# XJK1310-BT.net
KiCad netlist of a schematic drawn in EAGLE
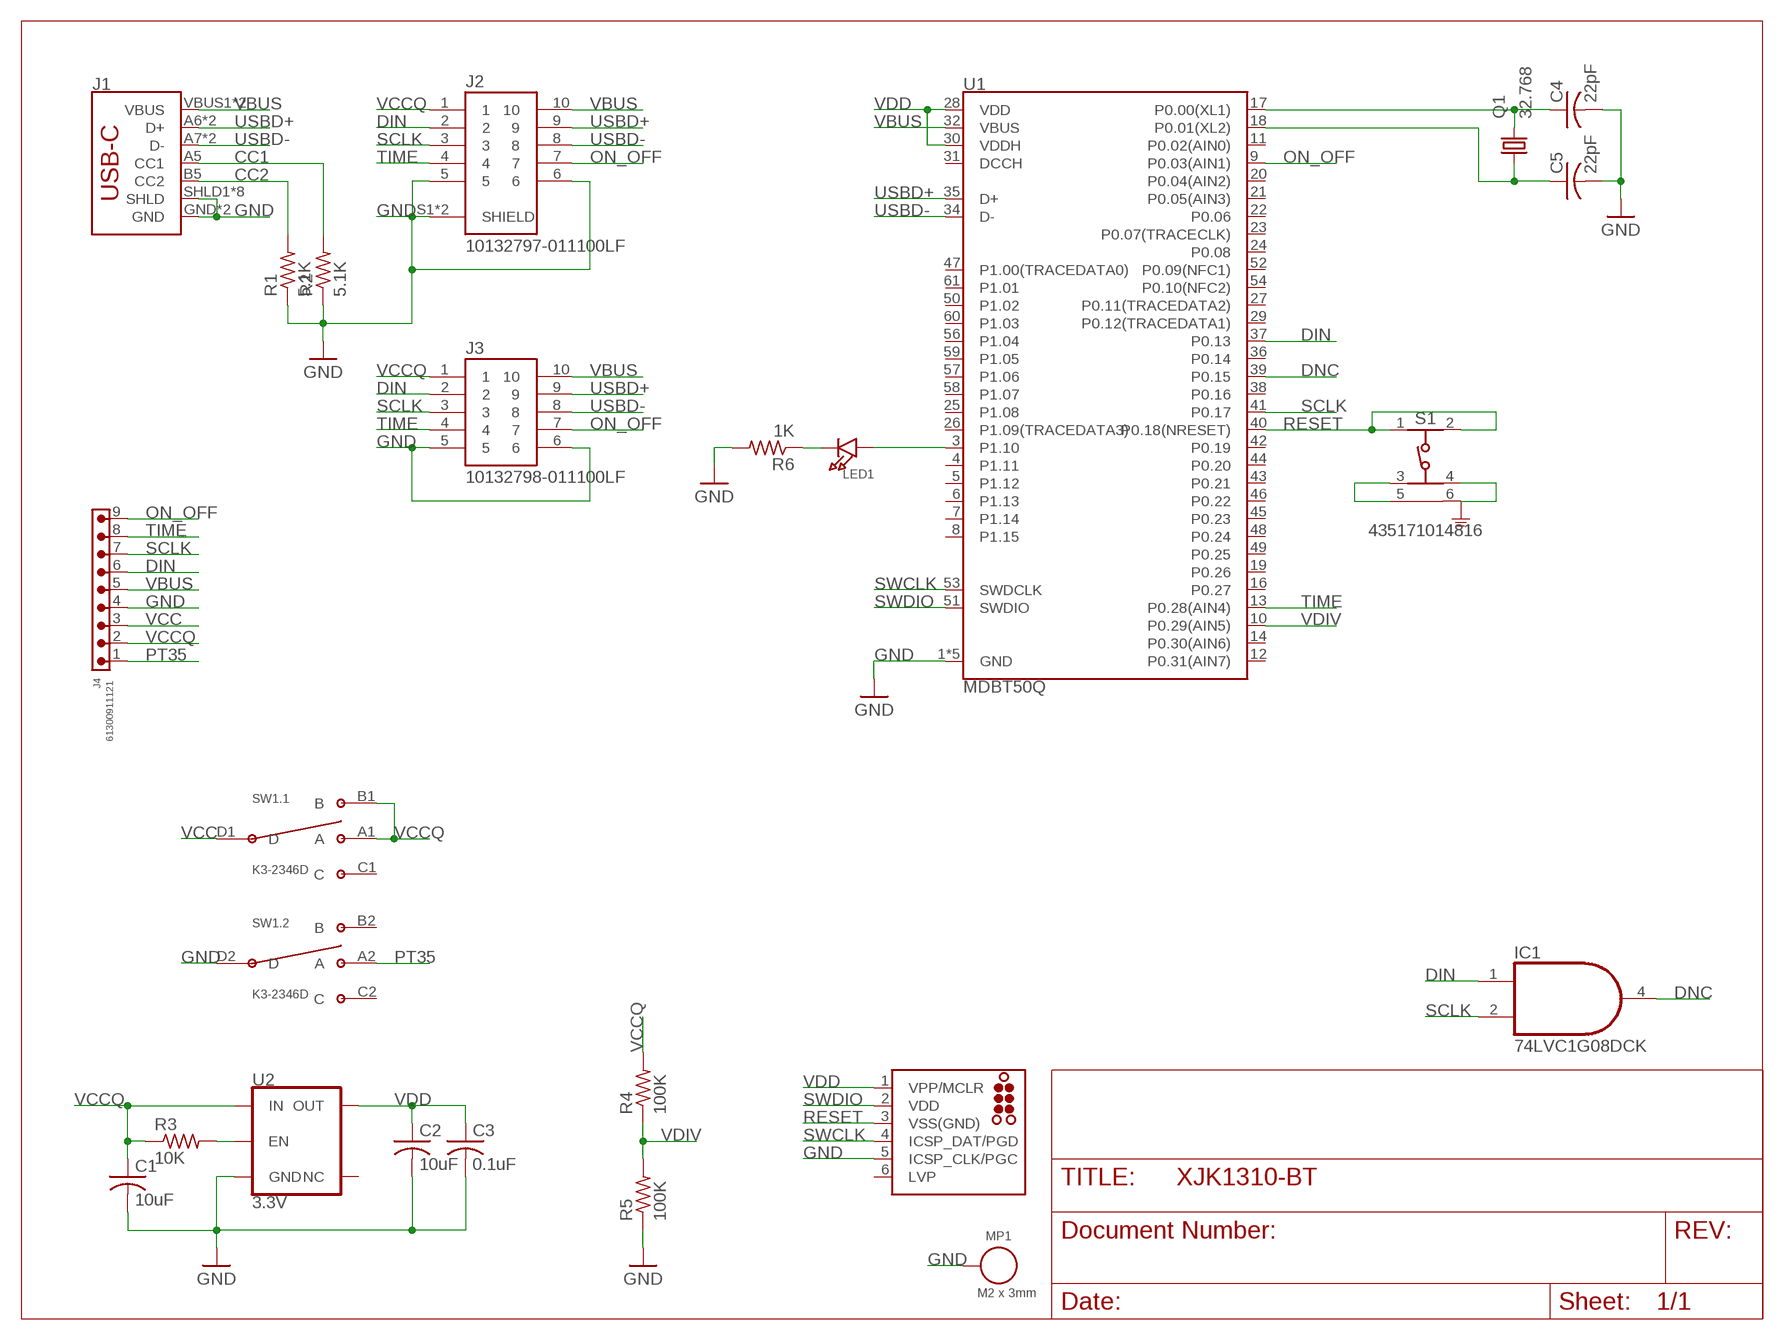
[diagram p0: schematic, sheet 1]

(export (version "E")
  (design (tool "Eeschema 10.0.6"))
  (components
    (comp (ref "C1")
      (value "10uF")
      (footprint "eagle-import:C0603")
      (libsource (lib "eagle-import") (part "C-USC0603"))
    )
    (comp (ref "C2")
      (value "10uF")
      (footprint "eagle-import:C0603")
      (libsource (lib "eagle-import") (part "C-USC0603"))
    )
    (comp (ref "C3")
      (value "0.1uF")
      (footprint "eagle-import:C0603")
      (libsource (lib "eagle-import") (part "C-USC0603"))
    )
    (comp (ref "C4")
      (value "22pF")
      (footprint "eagle-import:C0402")
      (libsource (lib "eagle-import") (part "C-USC0402"))
    )
    (comp (ref "C5")
      (value "22pF")
      (footprint "eagle-import:C0402")
      (libsource (lib "eagle-import") (part "C-USC0402"))
    )
    (comp (ref "IC1")
      (value "74LVC1G08DCK")
      (footprint "eagle-import:SC70-5")
      (libsource (lib "eagle-import") (part "741G08DCKLVC"))
    )
    (comp (ref "J1")
      (value "USB_C5")
      (footprint "eagle-import:USB-C-16P-5")
      (libsource (lib "eagle-import") (part "USB_C5"))
    )
    (comp (ref "J2")
      (value "10132797-011100LF")
      (footprint "eagle-import:AMPHENOL_10132797-011100LF")
      (fields (field (name "MANUFACTURER") "Amphenol"))
      (libsource (lib "eagle-import") (part "10132797-011100LF"))
    )
    (comp (ref "J3")
      (value "10132798-011100LF")
      (footprint "eagle-import:AMPHENOL_10132798-011100LF")
      (fields (field (name "MANUFACTURER") "Amphenol"))
      (libsource (lib "eagle-import") (part "10132798-011100LF"))
    )
    (comp (ref "J4")
      (value "61300911121")
      (footprint "eagle-import:61300911121")
      (libsource (lib "eagle-import") (part "6130XX11121_61300911121"))
    )
    (comp (ref "J5")
      (value "TC2030-MCP-NL")
      (footprint "eagle-import:TC2030-MCP-NL")
      (libsource (lib "eagle-import") (part "TC2030-MCP-NL"))
    )
    (comp (ref "LED1")
      (value "LED0805_NOOUTLINE")
      (footprint "eagle-import:CHIPLED_0805_NOOUTLINE")
      (libsource (lib "eagle-import") (part "LED0805_NOOUTLINE"))
    )
    (comp (ref "MP1")
      (value "M2 x 3mm")
      (footprint "eagle-import:WA-SMSI_9774030243")
      (libsource (lib "eagle-import") (part "WA-SMSI_9774XXX243_9774030243R"))
    )
    (comp (ref "Q1")
      (value "32.768")
      (footprint "eagle-import:3.2X1.5")
      (libsource (lib "eagle-import") (part "KX-327-NHF"))
    )
    (comp (ref "R1")
      (value "5.1K")
      (footprint "eagle-import:R0402")
      (libsource (lib "eagle-import") (part "R-US_R0402"))
    )
    (comp (ref "R2")
      (value "5.1K")
      (footprint "eagle-import:R0402")
      (libsource (lib "eagle-import") (part "R-US_R0402"))
    )
    (comp (ref "R3")
      (value "10K")
      (footprint "eagle-import:R0402")
      (libsource (lib "eagle-import") (part "R-US_R0402"))
    )
    (comp (ref "R4")
      (value "100K")
      (footprint "eagle-import:R0402")
      (libsource (lib "eagle-import") (part "R-US_R0402"))
    )
    (comp (ref "R5")
      (value "100K")
      (footprint "eagle-import:R0402")
      (libsource (lib "eagle-import") (part "R-US_R0402"))
    )
    (comp (ref "R6")
      (value "1K")
      (footprint "eagle-import:R0402")
      (libsource (lib "eagle-import") (part "R-US_R0402"))
    )
    (comp (ref "S1")
      (value "435171014816")
      (footprint "eagle-import:435171014816")
      (libsource (lib "eagle-import") (part "435171014816"))
    )
    (comp (ref "SW1")
      (value "K3-2346D")
      (footprint "eagle-import:K3-2346D")
      (fields (field (name "LCSC") "C145839"))
      (libsource (lib "eagle-import") (part "K3-2346D"))
    )
    (comp (ref "U1")
      (value "MDBT50Q")
      (footprint "eagle-import:MDBT50Q")
      (libsource (lib "eagle-import") (part "MDBT50Q"))
    )
    (comp (ref "U2")
      (value "3.3V")
      (footprint "eagle-import:SOT23-5")
      (libsource (lib "eagle-import") (part "V_REG_AP2112K-3.3V"))
    )
  )
  (nets
    (net (code "1") (name "/CC1") (class "Default")
      (node (ref "J1") (pin "A5") (pinfunction "CC1_A5") (pintype "bidirectional"))
      (node (ref "R2") (pin "2") (pinfunction "2_2") (pintype "passive"))
    )
    (net (code "2") (name "/CC2") (class "Default")
      (node (ref "J1") (pin "B5") (pinfunction "CC2_B5") (pintype "bidirectional"))
      (node (ref "R1") (pin "2") (pinfunction "2_2") (pintype "passive"))
    )
    (net (code "3") (name "/DIN") (class "Default")
      (node (ref "IC1") (pin "1") (pinfunction "I0_1") (pintype "input"))
      (node (ref "J2") (pin "2") (pinfunction "2_2") (pintype "passive"))
      (node (ref "J3") (pin "2") (pinfunction "2_2") (pintype "passive"))
      (node (ref "J4") (pin "6") (pinfunction "6_6") (pintype "passive"))
      (node (ref "U1") (pin "37") (pinfunction "P0.13_37") (pintype "bidirectional"))
    )
    (net (code "4") (name "/DNC") (class "Default")
      (node (ref "IC1") (pin "4") (pinfunction "O_4") (pintype "output"))
      (node (ref "U1") (pin "39") (pinfunction "P0.15_39") (pintype "bidirectional"))
    )
    (net (code "5") (name "/ON_OFF") (class "Default")
      (node (ref "J2") (pin "7") (pinfunction "7_7") (pintype "passive"))
      (node (ref "J3") (pin "7") (pinfunction "7_7") (pintype "passive"))
      (node (ref "J4") (pin "9") (pinfunction "9_9") (pintype "passive"))
      (node (ref "U1") (pin "9") (pinfunction "P0.03(AIN1)_9") (pintype "bidirectional"))
    )
    (net (code "6") (name "/PT35") (class "Default")
      (node (ref "J4") (pin "1") (pinfunction "1_1") (pintype "passive"))
      (node (ref "SW1") (pin "A2") (pinfunction "A_A2") (pintype "bidirectional"))
    )
    (net (code "7") (name "/RESET") (class "Default")
      (node (ref "J5") (pin "3") (pinfunction "VSS(GND)_3") (pintype "power_in"))
      (node (ref "S1") (pin "1") (pinfunction "1_1") (pintype "passive"))
      (node (ref "S1") (pin "2") (pinfunction "2_2") (pintype "passive"))
      (node (ref "U1") (pin "40") (pinfunction "P0.18(NRESET)_40") (pintype "bidirectional"))
    )
    (net (code "8") (name "/SCLK") (class "Default")
      (node (ref "IC1") (pin "2") (pinfunction "I1_2") (pintype "input"))
      (node (ref "J2") (pin "3") (pinfunction "3_3") (pintype "passive"))
      (node (ref "J3") (pin "3") (pinfunction "3_3") (pintype "passive"))
      (node (ref "J4") (pin "7") (pinfunction "7_7") (pintype "passive"))
      (node (ref "U1") (pin "41") (pinfunction "P0.17_41") (pintype "bidirectional"))
    )
    (net (code "9") (name "/SWCLK") (class "Default")
      (node (ref "J5") (pin "4") (pinfunction "ICSP_DAT/PGD_4") (pintype "bidirectional"))
      (node (ref "U1") (pin "53") (pinfunction "SWDCLK_53") (pintype "bidirectional"))
    )
    (net (code "10") (name "/SWDIO") (class "Default")
      (node (ref "J5") (pin "2") (pinfunction "VDD_2") (pintype "power_in"))
      (node (ref "U1") (pin "51") (pinfunction "SWDIO_51") (pintype "bidirectional"))
    )
    (net (code "11") (name "/TIME") (class "Default")
      (node (ref "J2") (pin "4") (pinfunction "4_4") (pintype "passive"))
      (node (ref "J3") (pin "4") (pinfunction "4_4") (pintype "passive"))
      (node (ref "J4") (pin "8") (pinfunction "8_8") (pintype "passive"))
      (node (ref "U1") (pin "13") (pinfunction "P0.28(AIN4)_13") (pintype "bidirectional"))
    )
    (net (code "12") (name "/USBD+") (class "Default")
      (node (ref "J1") (pin "A6") (pinfunction "D+_A6") (pintype "bidirectional"))
      (node (ref "J1") (pin "B6") (pinfunction "D+_B6") (pintype "bidirectional"))
      (node (ref "J2") (pin "9") (pinfunction "9_9") (pintype "passive"))
      (node (ref "J3") (pin "9") (pinfunction "9_9") (pintype "passive"))
      (node (ref "U1") (pin "35") (pinfunction "D+_35") (pintype "bidirectional"))
    )
    (net (code "13") (name "/USBD-") (class "Default")
      (node (ref "J1") (pin "A7") (pinfunction "D-_A7") (pintype "bidirectional"))
      (node (ref "J1") (pin "B7") (pinfunction "D-_B7") (pintype "bidirectional"))
      (node (ref "J2") (pin "8") (pinfunction "8_8") (pintype "passive"))
      (node (ref "J3") (pin "8") (pinfunction "8_8") (pintype "passive"))
      (node (ref "U1") (pin "34") (pinfunction "D-_34") (pintype "bidirectional"))
    )
    (net (code "14") (name "/VBUS") (class "Default")
      (node (ref "J1") (pin "VBUS1") (pinfunction "VBUS_VBUS1") (pintype "bidirectional"))
      (node (ref "J1") (pin "VBUS2") (pinfunction "VBUS_VBUS2") (pintype "bidirectional"))
      (node (ref "J2") (pin "10") (pinfunction "10_10") (pintype "passive"))
      (node (ref "J3") (pin "10") (pinfunction "10_10") (pintype "passive"))
      (node (ref "J4") (pin "5") (pinfunction "5_5") (pintype "passive"))
      (node (ref "U1") (pin "32") (pinfunction "VBUS_32") (pintype "bidirectional"))
    )
    (net (code "15") (name "/VCC") (class "Default")
      (node (ref "J4") (pin "3") (pinfunction "3_3") (pintype "passive"))
      (node (ref "SW1") (pin "D1") (pinfunction "D_D1") (pintype "bidirectional"))
    )
    (net (code "16") (name "/VCCQ") (class "Default")
      (node (ref "C1") (pin "1") (pinfunction "1_1") (pintype "passive"))
      (node (ref "J2") (pin "1") (pinfunction "1_1") (pintype "passive"))
      (node (ref "J3") (pin "1") (pinfunction "1_1") (pintype "passive"))
      (node (ref "J4") (pin "2") (pinfunction "2_2") (pintype "passive"))
      (node (ref "R3") (pin "1") (pinfunction "1_1") (pintype "passive"))
      (node (ref "R4") (pin "2") (pinfunction "2_2") (pintype "passive"))
      (node (ref "SW1") (pin "A1") (pinfunction "A_A1") (pintype "bidirectional"))
      (node (ref "SW1") (pin "B1") (pinfunction "B_B1") (pintype "bidirectional"))
      (node (ref "U2") (pin "1") (pinfunction "IN_1") (pintype "input"))
    )
    (net (code "17") (name "/VDD") (class "Default")
      (node (ref "C2") (pin "1") (pinfunction "1_1") (pintype "passive"))
      (node (ref "C3") (pin "1") (pinfunction "1_1") (pintype "passive"))
      (node (ref "J5") (pin "1") (pinfunction "VPP/MCLR_1") (pintype "passive"))
      (node (ref "U1") (pin "28") (pinfunction "VDD_28") (pintype "bidirectional"))
      (node (ref "U1") (pin "30") (pinfunction "VDDH_30") (pintype "bidirectional"))
      (node (ref "U2") (pin "5") (pinfunction "OUT_5") (pintype "passive"))
    )
    (net (code "18") (name "/VDIV") (class "Default")
      (node (ref "R4") (pin "1") (pinfunction "1_1") (pintype "passive"))
      (node (ref "R5") (pin "2") (pinfunction "2_2") (pintype "passive"))
      (node (ref "U1") (pin "10") (pinfunction "P0.29(AIN5)_10") (pintype "bidirectional"))
    )
    (net (code "19") (name "GND") (class "Default")
      (node (ref "C1") (pin "2") (pinfunction "2_2") (pintype "passive"))
      (node (ref "C2") (pin "2") (pinfunction "2_2") (pintype "passive"))
      (node (ref "C3") (pin "2") (pinfunction "2_2") (pintype "passive"))
      (node (ref "C4") (pin "2") (pinfunction "2_2") (pintype "passive"))
      (node (ref "C5") (pin "2") (pinfunction "2_2") (pintype "passive"))
      (node (ref "J1") (pin "GND") (pinfunction "GND_GND") (pintype "bidirectional"))
      (node (ref "J1") (pin "GND2") (pinfunction "GND_GND2") (pintype "bidirectional"))
      (node (ref "J1") (pin "SHLD1") (pinfunction "SHLD_SHLD1") (pintype "bidirectional"))
      (node (ref "J1") (pin "SHLD2") (pinfunction "SHLD_SHLD2") (pintype "bidirectional"))
      (node (ref "J1") (pin "SHLD3") (pinfunction "SHLD_SHLD3") (pintype "bidirectional"))
      (node (ref "J1") (pin "SHLD4") (pinfunction "SHLD_SHLD4") (pintype "bidirectional"))
      (node (ref "J1") (pin "SHLD5") (pinfunction "SHLD_SHLD5") (pintype "bidirectional"))
      (node (ref "J1") (pin "SHLD6") (pinfunction "SHLD_SHLD6") (pintype "bidirectional"))
      (node (ref "J1") (pin "SHLD7") (pinfunction "SHLD_SHLD7") (pintype "bidirectional"))
      (node (ref "J1") (pin "SHLD8") (pinfunction "SHLD_SHLD8") (pintype "bidirectional"))
      (node (ref "J2") (pin "5") (pinfunction "5_5") (pintype "passive"))
      (node (ref "J2") (pin "6") (pinfunction "6_6") (pintype "passive"))
      (node (ref "J2") (pin "S1") (pinfunction "SHIELD_S1") (pintype "passive"))
      (node (ref "J2") (pin "S2") (pinfunction "SHIELD_S2") (pintype "passive"))
      (node (ref "J3") (pin "5") (pinfunction "5_5") (pintype "passive"))
      (node (ref "J3") (pin "6") (pinfunction "6_6") (pintype "passive"))
      (node (ref "J4") (pin "4") (pinfunction "4_4") (pintype "passive"))
      (node (ref "J5") (pin "5") (pinfunction "ICSP_CLK/PGC_5") (pintype "output"))
      (node (ref "MP1") (pin "1") (pinfunction "1_1") (pintype "passive"))
      (node (ref "R1") (pin "1") (pinfunction "1_1") (pintype "passive"))
      (node (ref "R2") (pin "1") (pinfunction "1_1") (pintype "passive"))
      (node (ref "R5") (pin "1") (pinfunction "1_1") (pintype "passive"))
      (node (ref "R6") (pin "2") (pinfunction "2_2") (pintype "passive"))
      (node (ref "S1") (pin "3") (pinfunction "3_3") (pintype "passive"))
      (node (ref "S1") (pin "4") (pinfunction "4_4") (pintype "passive"))
      (node (ref "S1") (pin "5") (pinfunction "5_5") (pintype "passive"))
      (node (ref "S1") (pin "6") (pinfunction "6_6") (pintype "passive"))
      (node (ref "SW1") (pin "D2") (pinfunction "D_D2") (pintype "bidirectional"))
      (node (ref "U1") (pin "1") (pinfunction "GND_1") (pintype "bidirectional"))
      (node (ref "U1") (pin "15") (pinfunction "GND_15") (pintype "bidirectional"))
      (node (ref "U1") (pin "2") (pinfunction "GND_2") (pintype "bidirectional"))
      (node (ref "U1") (pin "33") (pinfunction "GND_33") (pintype "bidirectional"))
      (node (ref "U1") (pin "55") (pinfunction "GND_55") (pintype "bidirectional"))
      (node (ref "U2") (pin "2") (pinfunction "GND_2") (pintype "input"))
    )
    (net (code "20") (name "Net-(LED1-PadC)") (class "Default")
      (node (ref "LED1") (pin "C") (pinfunction "C_C") (pintype "passive"))
      (node (ref "R6") (pin "1") (pinfunction "1_1") (pintype "passive"))
    )
    (net (code "21") (name "Net-(U1-P0.00(XL1))") (class "Default")
      (node (ref "C4") (pin "1") (pinfunction "1_1") (pintype "passive"))
      (node (ref "Q1") (pin "2") (pinfunction "2_2") (pintype "passive"))
      (node (ref "U1") (pin "17") (pinfunction "P0.00(XL1)_17") (pintype "bidirectional"))
    )
    (net (code "22") (name "Net-(U1-P0.01(XL2))") (class "Default")
      (node (ref "C5") (pin "1") (pinfunction "1_1") (pintype "passive"))
      (node (ref "Q1") (pin "1") (pinfunction "1_1") (pintype "passive"))
      (node (ref "U1") (pin "18") (pinfunction "P0.01(XL2)_18") (pintype "bidirectional"))
    )
    (net (code "23") (name "Net-(U1-P1.10)") (class "Default")
      (node (ref "LED1") (pin "A") (pinfunction "A_A") (pintype "passive"))
      (node (ref "U1") (pin "3") (pinfunction "P1.10_3") (pintype "bidirectional"))
    )
    (net (code "24") (name "Net-(U2-EN)") (class "Default")
      (node (ref "R3") (pin "2") (pinfunction "2_2") (pintype "passive"))
      (node (ref "U2") (pin "3") (pinfunction "EN_3") (pintype "input"))
    )
    (net (code "25") (name "unconnected-(J5-LVP-Pad6)") (class "Default")
      (node (ref "J5") (pin "6") (pinfunction "LVP_6") (pintype "bidirectional"))
    )
    (net (code "26") (name "unconnected-(SW1A-C-PadC1)") (class "Default")
      (node (ref "SW1") (pin "C1") (pinfunction "C_C1") (pintype "bidirectional"))
    )
    (net (code "27") (name "unconnected-(SW1B-B-PadB2)") (class "Default")
      (node (ref "SW1") (pin "B2") (pinfunction "B_B2") (pintype "bidirectional"))
    )
    (net (code "28") (name "unconnected-(SW1B-C-PadC2)") (class "Default")
      (node (ref "SW1") (pin "C2") (pinfunction "C_C2") (pintype "bidirectional"))
    )
    (net (code "29") (name "unconnected-(U1-DCCH-Pad31)") (class "Default")
      (node (ref "U1") (pin "31") (pinfunction "DCCH_31") (pintype "bidirectional"))
    )
    (net (code "30") (name "unconnected-(U1-P0.02(AIN0)-Pad11)") (class "Default")
      (node (ref "U1") (pin "11") (pinfunction "P0.02(AIN0)_11") (pintype "bidirectional"))
    )
    (net (code "31") (name "unconnected-(U1-P0.04(AIN2)-Pad20)") (class "Default")
      (node (ref "U1") (pin "20") (pinfunction "P0.04(AIN2)_20") (pintype "bidirectional"))
    )
    (net (code "32") (name "unconnected-(U1-P0.05(AIN3)-Pad21)") (class "Default")
      (node (ref "U1") (pin "21") (pinfunction "P0.05(AIN3)_21") (pintype "bidirectional"))
    )
    (net (code "33") (name "unconnected-(U1-P0.06-Pad22)") (class "Default")
      (node (ref "U1") (pin "22") (pinfunction "P0.06_22") (pintype "bidirectional"))
    )
    (net (code "34") (name "unconnected-(U1-P0.07(TRACECLK)-Pad23)") (class "Default")
      (node (ref "U1") (pin "23") (pinfunction "P0.07(TRACECLK)_23") (pintype "bidirectional"))
    )
    (net (code "35") (name "unconnected-(U1-P0.08-Pad24)") (class "Default")
      (node (ref "U1") (pin "24") (pinfunction "P0.08_24") (pintype "bidirectional"))
    )
    (net (code "36") (name "unconnected-(U1-P0.09(NFC1)-Pad52)") (class "Default")
      (node (ref "U1") (pin "52") (pinfunction "P0.09(NFC1)_52") (pintype "bidirectional"))
    )
    (net (code "37") (name "unconnected-(U1-P0.10(NFC2)-Pad54)") (class "Default")
      (node (ref "U1") (pin "54") (pinfunction "P0.10(NFC2)_54") (pintype "bidirectional"))
    )
    (net (code "38") (name "unconnected-(U1-P0.11(TRACEDATA2)-Pad27)") (class "Default")
      (node (ref "U1") (pin "27") (pinfunction "P0.11(TRACEDATA2)_27") (pintype "bidirectional"))
    )
    (net (code "39") (name "unconnected-(U1-P0.12(TRACEDATA1)-Pad29)") (class "Default")
      (node (ref "U1") (pin "29") (pinfunction "P0.12(TRACEDATA1)_29") (pintype "bidirectional"))
    )
    (net (code "40") (name "unconnected-(U1-P0.14-Pad36)") (class "Default")
      (node (ref "U1") (pin "36") (pinfunction "P0.14_36") (pintype "bidirectional"))
    )
    (net (code "41") (name "unconnected-(U1-P0.16-Pad38)") (class "Default")
      (node (ref "U1") (pin "38") (pinfunction "P0.16_38") (pintype "bidirectional"))
    )
    (net (code "42") (name "unconnected-(U1-P0.19-Pad42)") (class "Default")
      (node (ref "U1") (pin "42") (pinfunction "P0.19_42") (pintype "bidirectional"))
    )
    (net (code "43") (name "unconnected-(U1-P0.20-Pad44)") (class "Default")
      (node (ref "U1") (pin "44") (pinfunction "P0.20_44") (pintype "bidirectional"))
    )
    (net (code "44") (name "unconnected-(U1-P0.21-Pad43)") (class "Default")
      (node (ref "U1") (pin "43") (pinfunction "P0.21_43") (pintype "bidirectional"))
    )
    (net (code "45") (name "unconnected-(U1-P0.22-Pad46)") (class "Default")
      (node (ref "U1") (pin "46") (pinfunction "P0.22_46") (pintype "bidirectional"))
    )
    (net (code "46") (name "unconnected-(U1-P0.23-Pad45)") (class "Default")
      (node (ref "U1") (pin "45") (pinfunction "P0.23_45") (pintype "bidirectional"))
    )
    (net (code "47") (name "unconnected-(U1-P0.24-Pad48)") (class "Default")
      (node (ref "U1") (pin "48") (pinfunction "P0.24_48") (pintype "bidirectional"))
    )
    (net (code "48") (name "unconnected-(U1-P0.25-Pad49)") (class "Default")
      (node (ref "U1") (pin "49") (pinfunction "P0.25_49") (pintype "bidirectional"))
    )
    (net (code "49") (name "unconnected-(U1-P0.26-Pad19)") (class "Default")
      (node (ref "U1") (pin "19") (pinfunction "P0.26_19") (pintype "bidirectional"))
    )
    (net (code "50") (name "unconnected-(U1-P0.27-Pad16)") (class "Default")
      (node (ref "U1") (pin "16") (pinfunction "P0.27_16") (pintype "bidirectional"))
    )
    (net (code "51") (name "unconnected-(U1-P0.30(AIN6)-Pad14)") (class "Default")
      (node (ref "U1") (pin "14") (pinfunction "P0.30(AIN6)_14") (pintype "bidirectional"))
    )
    (net (code "52") (name "unconnected-(U1-P0.31(AIN7)-Pad12)") (class "Default")
      (node (ref "U1") (pin "12") (pinfunction "P0.31(AIN7)_12") (pintype "bidirectional"))
    )
    (net (code "53") (name "unconnected-(U1-P1.00(TRACEDATA0)-Pad47)") (class "Default")
      (node (ref "U1") (pin "47") (pinfunction "P1.00(TRACEDATA0)_47") (pintype "bidirectional"))
    )
    (net (code "54") (name "unconnected-(U1-P1.01-Pad61)") (class "Default")
      (node (ref "U1") (pin "61") (pinfunction "P1.01_61") (pintype "bidirectional"))
    )
    (net (code "55") (name "unconnected-(U1-P1.02-Pad50)") (class "Default")
      (node (ref "U1") (pin "50") (pinfunction "P1.02_50") (pintype "bidirectional"))
    )
    (net (code "56") (name "unconnected-(U1-P1.03-Pad60)") (class "Default")
      (node (ref "U1") (pin "60") (pinfunction "P1.03_60") (pintype "bidirectional"))
    )
    (net (code "57") (name "unconnected-(U1-P1.04-Pad56)") (class "Default")
      (node (ref "U1") (pin "56") (pinfunction "P1.04_56") (pintype "bidirectional"))
    )
    (net (code "58") (name "unconnected-(U1-P1.05-Pad59)") (class "Default")
      (node (ref "U1") (pin "59") (pinfunction "P1.05_59") (pintype "bidirectional"))
    )
    (net (code "59") (name "unconnected-(U1-P1.06-Pad57)") (class "Default")
      (node (ref "U1") (pin "57") (pinfunction "P1.06_57") (pintype "bidirectional"))
    )
    (net (code "60") (name "unconnected-(U1-P1.07-Pad58)") (class "Default")
      (node (ref "U1") (pin "58") (pinfunction "P1.07_58") (pintype "bidirectional"))
    )
    (net (code "61") (name "unconnected-(U1-P1.08-Pad25)") (class "Default")
      (node (ref "U1") (pin "25") (pinfunction "P1.08_25") (pintype "bidirectional"))
    )
    (net (code "62") (name "unconnected-(U1-P1.09(TRACEDATA3)-Pad26)") (class "Default")
      (node (ref "U1") (pin "26") (pinfunction "P1.09(TRACEDATA3)_26") (pintype "bidirectional"))
    )
    (net (code "63") (name "unconnected-(U1-P1.11-Pad4)") (class "Default")
      (node (ref "U1") (pin "4") (pinfunction "P1.11_4") (pintype "bidirectional"))
    )
    (net (code "64") (name "unconnected-(U1-P1.12-Pad5)") (class "Default")
      (node (ref "U1") (pin "5") (pinfunction "P1.12_5") (pintype "bidirectional"))
    )
    (net (code "65") (name "unconnected-(U1-P1.13-Pad6)") (class "Default")
      (node (ref "U1") (pin "6") (pinfunction "P1.13_6") (pintype "bidirectional"))
    )
    (net (code "66") (name "unconnected-(U1-P1.14-Pad7)") (class "Default")
      (node (ref "U1") (pin "7") (pinfunction "P1.14_7") (pintype "bidirectional"))
    )
    (net (code "67") (name "unconnected-(U1-P1.15-Pad8)") (class "Default")
      (node (ref "U1") (pin "8") (pinfunction "P1.15_8") (pintype "bidirectional"))
    )
    (net (code "68") (name "unconnected-(U2-NC-Pad4)") (class "Default")
      (node (ref "U2") (pin "4") (pinfunction "NC_4") (pintype "no_connect"))
    )
  )
)
